# xcr3064xl_breakout.net
KiCad netlist of a schematic drawn in EAGLE
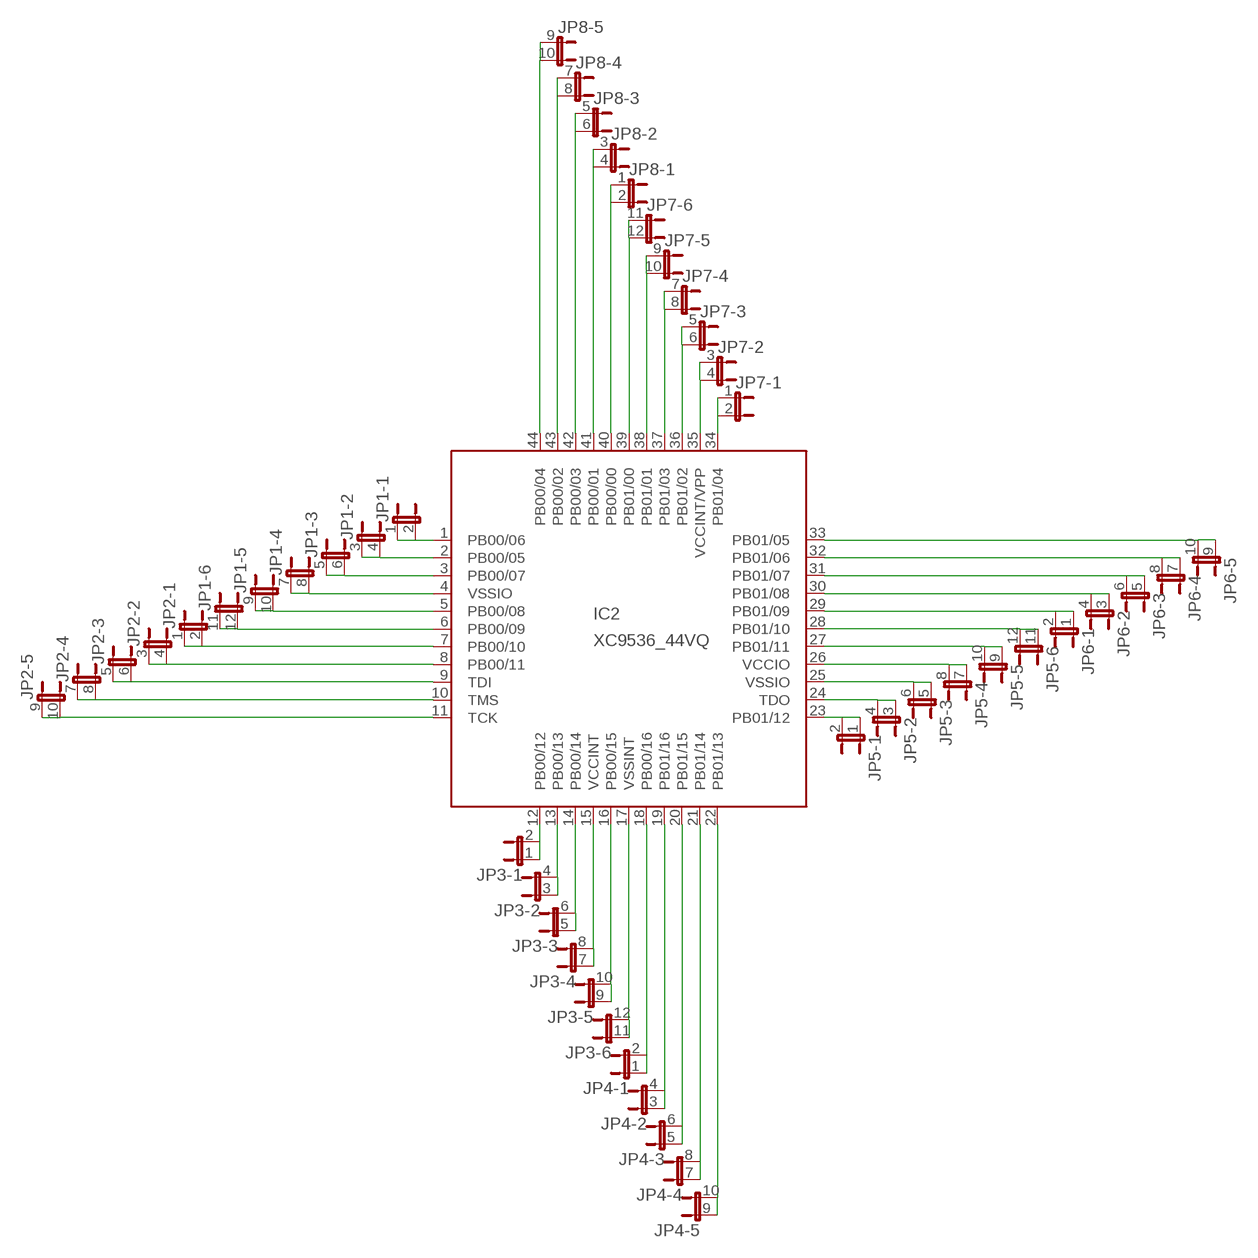
[diagram p0: schematic, sheet 1]

(export (version "E")
  (design (tool "Eeschema 10.0.6"))
  (components
    (comp (ref "IC2")
      (value "XC9536_44VQ")
      (footprint "eagle-import:SQFP-S-10X10-44")
      (fields (field (name "MPN") "XC9536-15VQG44C"))
      (libsource (lib "eagle-import") (part "XC9536_44VQ"))
    )
    (comp (ref "JP1")
      (value "JP6QE")
      (footprint "eagle-import:JP6Q")
      (libsource (lib "eagle-import") (part "JP6QE"))
    )
    (comp (ref "JP2")
      (value "JP6QE")
      (footprint "eagle-import:JP6Q")
      (libsource (lib "eagle-import") (part "JP6QE"))
    )
    (comp (ref "JP3")
      (value "JP6QE")
      (footprint "eagle-import:JP6Q")
      (libsource (lib "eagle-import") (part "JP6QE"))
    )
    (comp (ref "JP4")
      (value "JP6QE")
      (footprint "eagle-import:JP6Q")
      (libsource (lib "eagle-import") (part "JP6QE"))
    )
    (comp (ref "JP5")
      (value "JP6QE")
      (footprint "eagle-import:JP6Q")
      (libsource (lib "eagle-import") (part "JP6QE"))
    )
    (comp (ref "JP6")
      (value "JP6QE")
      (footprint "eagle-import:JP6Q")
      (libsource (lib "eagle-import") (part "JP6QE"))
    )
    (comp (ref "JP7")
      (value "JP6QE")
      (footprint "eagle-import:JP6Q")
      (libsource (lib "eagle-import") (part "JP6QE"))
    )
    (comp (ref "JP8")
      (value "JP6QE")
      (footprint "eagle-import:JP6Q")
      (libsource (lib "eagle-import") (part "JP6QE"))
    )
  )
  (nets
    (net (code "1") (name "Net-(IC2-PB00{slash}00)") (class "Default")
      (node (ref "IC2") (pin "40") (pinfunction "PB00/00_40") (pintype "bidirectional"))
      (node (ref "JP8") (pin "1") (pinfunction "1_1") (pintype "passive"))
      (node (ref "JP8") (pin "2") (pinfunction "2_2") (pintype "passive"))
    )
    (net (code "2") (name "Net-(IC2-PB00{slash}01)") (class "Default")
      (node (ref "IC2") (pin "41") (pinfunction "PB00/01_41") (pintype "bidirectional"))
      (node (ref "JP8") (pin "3") (pinfunction "1_3") (pintype "passive"))
      (node (ref "JP8") (pin "4") (pinfunction "2_4") (pintype "passive"))
    )
    (net (code "3") (name "Net-(IC2-PB00{slash}02)") (class "Default")
      (node (ref "IC2") (pin "43") (pinfunction "PB00/02_43") (pintype "bidirectional"))
      (node (ref "JP8") (pin "7") (pinfunction "1_7") (pintype "passive"))
      (node (ref "JP8") (pin "8") (pinfunction "2_8") (pintype "passive"))
    )
    (net (code "4") (name "Net-(IC2-PB00{slash}03)") (class "Default")
      (node (ref "IC2") (pin "42") (pinfunction "PB00/03_42") (pintype "bidirectional"))
      (node (ref "JP8") (pin "5") (pinfunction "1_5") (pintype "passive"))
      (node (ref "JP8") (pin "6") (pinfunction "2_6") (pintype "passive"))
    )
    (net (code "5") (name "Net-(IC2-PB00{slash}04)") (class "Default")
      (node (ref "IC2") (pin "44") (pinfunction "PB00/04_44") (pintype "bidirectional"))
      (node (ref "JP8") (pin "10") (pinfunction "2_10") (pintype "passive"))
      (node (ref "JP8") (pin "9") (pinfunction "1_9") (pintype "passive"))
    )
    (net (code "6") (name "Net-(IC2-PB00{slash}05)") (class "Default")
      (node (ref "IC2") (pin "2") (pinfunction "PB00/05_2") (pintype "bidirectional"))
      (node (ref "JP1") (pin "3") (pinfunction "1_3") (pintype "passive"))
      (node (ref "JP1") (pin "4") (pinfunction "2_4") (pintype "passive"))
    )
    (net (code "7") (name "Net-(IC2-PB00{slash}06)") (class "Default")
      (node (ref "IC2") (pin "1") (pinfunction "PB00/06_1") (pintype "bidirectional"))
      (node (ref "JP1") (pin "1") (pinfunction "1_1") (pintype "passive"))
      (node (ref "JP1") (pin "2") (pinfunction "2_2") (pintype "passive"))
    )
    (net (code "8") (name "Net-(IC2-PB00{slash}07)") (class "Default")
      (node (ref "IC2") (pin "3") (pinfunction "PB00/07_3") (pintype "bidirectional"))
      (node (ref "JP1") (pin "5") (pinfunction "1_5") (pintype "passive"))
      (node (ref "JP1") (pin "6") (pinfunction "2_6") (pintype "passive"))
    )
    (net (code "9") (name "Net-(IC2-PB00{slash}08)") (class "Default")
      (node (ref "IC2") (pin "5") (pinfunction "PB00/08_5") (pintype "bidirectional"))
      (node (ref "JP1") (pin "10") (pinfunction "2_10") (pintype "passive"))
      (node (ref "JP1") (pin "9") (pinfunction "1_9") (pintype "passive"))
    )
    (net (code "10") (name "Net-(IC2-PB00{slash}09)") (class "Default")
      (node (ref "IC2") (pin "6") (pinfunction "PB00/09_6") (pintype "bidirectional"))
      (node (ref "JP1") (pin "11") (pinfunction "1_11") (pintype "passive"))
      (node (ref "JP1") (pin "12") (pinfunction "2_12") (pintype "passive"))
    )
    (net (code "11") (name "Net-(IC2-PB00{slash}10)") (class "Default")
      (node (ref "IC2") (pin "7") (pinfunction "PB00/10_7") (pintype "bidirectional"))
      (node (ref "JP2") (pin "1") (pinfunction "1_1") (pintype "passive"))
      (node (ref "JP2") (pin "2") (pinfunction "2_2") (pintype "passive"))
    )
    (net (code "12") (name "Net-(IC2-PB00{slash}11)") (class "Default")
      (node (ref "IC2") (pin "8") (pinfunction "PB00/11_8") (pintype "bidirectional"))
      (node (ref "JP2") (pin "3") (pinfunction "1_3") (pintype "passive"))
      (node (ref "JP2") (pin "4") (pinfunction "2_4") (pintype "passive"))
    )
    (net (code "13") (name "Net-(IC2-PB00{slash}12)") (class "Default")
      (node (ref "IC2") (pin "12") (pinfunction "PB00/12_12") (pintype "bidirectional"))
      (node (ref "JP3") (pin "1") (pinfunction "1_1") (pintype "passive"))
      (node (ref "JP3") (pin "2") (pinfunction "2_2") (pintype "passive"))
    )
    (net (code "14") (name "Net-(IC2-PB00{slash}13)") (class "Default")
      (node (ref "IC2") (pin "13") (pinfunction "PB00/13_13") (pintype "bidirectional"))
      (node (ref "JP3") (pin "3") (pinfunction "1_3") (pintype "passive"))
      (node (ref "JP3") (pin "4") (pinfunction "2_4") (pintype "passive"))
    )
    (net (code "15") (name "Net-(IC2-PB00{slash}14)") (class "Default")
      (node (ref "IC2") (pin "14") (pinfunction "PB00/14_14") (pintype "bidirectional"))
      (node (ref "JP3") (pin "5") (pinfunction "1_5") (pintype "passive"))
      (node (ref "JP3") (pin "6") (pinfunction "2_6") (pintype "passive"))
    )
    (net (code "16") (name "Net-(IC2-PB00{slash}15)") (class "Default")
      (node (ref "IC2") (pin "16") (pinfunction "PB00/15_16") (pintype "bidirectional"))
      (node (ref "JP3") (pin "10") (pinfunction "2_10") (pintype "passive"))
      (node (ref "JP3") (pin "9") (pinfunction "1_9") (pintype "passive"))
    )
    (net (code "17") (name "Net-(IC2-PB00{slash}16)") (class "Default")
      (node (ref "IC2") (pin "18") (pinfunction "PB00/16_18") (pintype "bidirectional"))
      (node (ref "JP4") (pin "1") (pinfunction "1_1") (pintype "passive"))
      (node (ref "JP4") (pin "2") (pinfunction "2_2") (pintype "passive"))
    )
    (net (code "18") (name "Net-(IC2-PB01{slash}00)") (class "Default")
      (node (ref "IC2") (pin "39") (pinfunction "PB01/00_39") (pintype "bidirectional"))
      (node (ref "JP7") (pin "11") (pinfunction "1_11") (pintype "passive"))
      (node (ref "JP7") (pin "12") (pinfunction "2_12") (pintype "passive"))
    )
    (net (code "19") (name "Net-(IC2-PB01{slash}01)") (class "Default")
      (node (ref "IC2") (pin "38") (pinfunction "PB01/01_38") (pintype "bidirectional"))
      (node (ref "JP7") (pin "10") (pinfunction "2_10") (pintype "passive"))
      (node (ref "JP7") (pin "9") (pinfunction "1_9") (pintype "passive"))
    )
    (net (code "20") (name "Net-(IC2-PB01{slash}02)") (class "Default")
      (node (ref "IC2") (pin "36") (pinfunction "PB01/02_36") (pintype "bidirectional"))
      (node (ref "JP7") (pin "5") (pinfunction "1_5") (pintype "passive"))
      (node (ref "JP7") (pin "6") (pinfunction "2_6") (pintype "passive"))
    )
    (net (code "21") (name "Net-(IC2-PB01{slash}03)") (class "Default")
      (node (ref "IC2") (pin "37") (pinfunction "PB01/03_37") (pintype "bidirectional"))
      (node (ref "JP7") (pin "7") (pinfunction "1_7") (pintype "passive"))
      (node (ref "JP7") (pin "8") (pinfunction "2_8") (pintype "passive"))
    )
    (net (code "22") (name "Net-(IC2-PB01{slash}04)") (class "Default")
      (node (ref "IC2") (pin "34") (pinfunction "PB01/04_34") (pintype "bidirectional"))
      (node (ref "JP7") (pin "1") (pinfunction "1_1") (pintype "passive"))
      (node (ref "JP7") (pin "2") (pinfunction "2_2") (pintype "passive"))
    )
    (net (code "23") (name "Net-(IC2-PB01{slash}05)") (class "Default")
      (node (ref "IC2") (pin "33") (pinfunction "PB01/05_33") (pintype "bidirectional"))
      (node (ref "JP6") (pin "10") (pinfunction "2_10") (pintype "passive"))
      (node (ref "JP6") (pin "9") (pinfunction "1_9") (pintype "passive"))
    )
    (net (code "24") (name "Net-(IC2-PB01{slash}06)") (class "Default")
      (node (ref "IC2") (pin "32") (pinfunction "PB01/06_32") (pintype "bidirectional"))
      (node (ref "JP6") (pin "7") (pinfunction "1_7") (pintype "passive"))
      (node (ref "JP6") (pin "8") (pinfunction "2_8") (pintype "passive"))
    )
    (net (code "25") (name "Net-(IC2-PB01{slash}07)") (class "Default")
      (node (ref "IC2") (pin "31") (pinfunction "PB01/07_31") (pintype "bidirectional"))
      (node (ref "JP6") (pin "5") (pinfunction "1_5") (pintype "passive"))
      (node (ref "JP6") (pin "6") (pinfunction "2_6") (pintype "passive"))
    )
    (net (code "26") (name "Net-(IC2-PB01{slash}08)") (class "Default")
      (node (ref "IC2") (pin "30") (pinfunction "PB01/08_30") (pintype "bidirectional"))
      (node (ref "JP6") (pin "3") (pinfunction "1_3") (pintype "passive"))
      (node (ref "JP6") (pin "4") (pinfunction "2_4") (pintype "passive"))
    )
    (net (code "27") (name "Net-(IC2-PB01{slash}09)") (class "Default")
      (node (ref "IC2") (pin "29") (pinfunction "PB01/09_29") (pintype "bidirectional"))
      (node (ref "JP6") (pin "1") (pinfunction "1_1") (pintype "passive"))
      (node (ref "JP6") (pin "2") (pinfunction "2_2") (pintype "passive"))
    )
    (net (code "28") (name "Net-(IC2-PB01{slash}10)") (class "Default")
      (node (ref "IC2") (pin "28") (pinfunction "PB01/10_28") (pintype "bidirectional"))
      (node (ref "JP5") (pin "11") (pinfunction "1_11") (pintype "passive"))
      (node (ref "JP5") (pin "12") (pinfunction "2_12") (pintype "passive"))
    )
    (net (code "29") (name "Net-(IC2-PB01{slash}11)") (class "Default")
      (node (ref "IC2") (pin "27") (pinfunction "PB01/11_27") (pintype "bidirectional"))
      (node (ref "JP5") (pin "10") (pinfunction "2_10") (pintype "passive"))
      (node (ref "JP5") (pin "9") (pinfunction "1_9") (pintype "passive"))
    )
    (net (code "30") (name "Net-(IC2-PB01{slash}12)") (class "Default")
      (node (ref "IC2") (pin "23") (pinfunction "PB01/12_23") (pintype "bidirectional"))
      (node (ref "JP5") (pin "1") (pinfunction "1_1") (pintype "passive"))
      (node (ref "JP5") (pin "2") (pinfunction "2_2") (pintype "passive"))
    )
    (net (code "31") (name "Net-(IC2-PB01{slash}13)") (class "Default")
      (node (ref "IC2") (pin "22") (pinfunction "PB01/13_22") (pintype "bidirectional"))
      (node (ref "JP4") (pin "10") (pinfunction "2_10") (pintype "passive"))
      (node (ref "JP4") (pin "9") (pinfunction "1_9") (pintype "passive"))
    )
    (net (code "32") (name "Net-(IC2-PB01{slash}14)") (class "Default")
      (node (ref "IC2") (pin "21") (pinfunction "PB01/14_21") (pintype "bidirectional"))
      (node (ref "JP4") (pin "7") (pinfunction "1_7") (pintype "passive"))
      (node (ref "JP4") (pin "8") (pinfunction "2_8") (pintype "passive"))
    )
    (net (code "33") (name "Net-(IC2-PB01{slash}15)") (class "Default")
      (node (ref "IC2") (pin "20") (pinfunction "PB01/15_20") (pintype "bidirectional"))
      (node (ref "JP4") (pin "5") (pinfunction "1_5") (pintype "passive"))
      (node (ref "JP4") (pin "6") (pinfunction "2_6") (pintype "passive"))
    )
    (net (code "34") (name "Net-(IC2-PB01{slash}16)") (class "Default")
      (node (ref "IC2") (pin "19") (pinfunction "PB01/16_19") (pintype "bidirectional"))
      (node (ref "JP4") (pin "3") (pinfunction "1_3") (pintype "passive"))
      (node (ref "JP4") (pin "4") (pinfunction "2_4") (pintype "passive"))
    )
    (net (code "35") (name "Net-(IC2-TCK)") (class "Default")
      (node (ref "IC2") (pin "11") (pinfunction "TCK_11") (pintype "input"))
      (node (ref "JP2") (pin "10") (pinfunction "2_10") (pintype "passive"))
      (node (ref "JP2") (pin "9") (pinfunction "1_9") (pintype "passive"))
    )
    (net (code "36") (name "Net-(IC2-TDI)") (class "Default")
      (node (ref "IC2") (pin "9") (pinfunction "TDI_9") (pintype "input"))
      (node (ref "JP2") (pin "5") (pinfunction "1_5") (pintype "passive"))
      (node (ref "JP2") (pin "6") (pinfunction "2_6") (pintype "passive"))
    )
    (net (code "37") (name "Net-(IC2-TDO)") (class "Default")
      (node (ref "IC2") (pin "24") (pinfunction "TDO_24") (pintype "output"))
      (node (ref "JP5") (pin "3") (pinfunction "1_3") (pintype "passive"))
      (node (ref "JP5") (pin "4") (pinfunction "2_4") (pintype "passive"))
    )
    (net (code "38") (name "Net-(IC2-TMS)") (class "Default")
      (node (ref "IC2") (pin "10") (pinfunction "TMS_10") (pintype "input"))
      (node (ref "JP2") (pin "7") (pinfunction "1_7") (pintype "passive"))
      (node (ref "JP2") (pin "8") (pinfunction "2_8") (pintype "passive"))
    )
    (net (code "39") (name "Net-(IC2-VCCINT)") (class "Default")
      (node (ref "IC2") (pin "15") (pinfunction "VCCINT_15") (pintype "power_in"))
      (node (ref "JP3") (pin "7") (pinfunction "1_7") (pintype "passive"))
      (node (ref "JP3") (pin "8") (pinfunction "2_8") (pintype "passive"))
    )
    (net (code "40") (name "Net-(IC2-VCCINT{slash}VPP)") (class "Default")
      (node (ref "IC2") (pin "35") (pinfunction "VCCINT/VPP_35") (pintype "input"))
      (node (ref "JP7") (pin "3") (pinfunction "1_3") (pintype "passive"))
      (node (ref "JP7") (pin "4") (pinfunction "2_4") (pintype "passive"))
    )
    (net (code "41") (name "Net-(IC2-VCCIO)") (class "Default")
      (node (ref "IC2") (pin "26") (pinfunction "VCCIO_26") (pintype "power_in"))
      (node (ref "JP5") (pin "7") (pinfunction "1_7") (pintype "passive"))
      (node (ref "JP5") (pin "8") (pinfunction "2_8") (pintype "passive"))
    )
    (net (code "42") (name "Net-(IC2-VSSINT)") (class "Default")
      (node (ref "IC2") (pin "17") (pinfunction "VSSINT_17") (pintype "power_in"))
      (node (ref "JP3") (pin "11") (pinfunction "1_11") (pintype "passive"))
      (node (ref "JP3") (pin "12") (pinfunction "2_12") (pintype "passive"))
    )
    (net (code "43") (name "Net-(JP1D-1)") (class "Default")
      (node (ref "IC2") (pin "4") (pinfunction "VSSIO_4") (pintype "power_in"))
      (node (ref "JP1") (pin "7") (pinfunction "1_7") (pintype "passive"))
      (node (ref "JP1") (pin "8") (pinfunction "2_8") (pintype "passive"))
    )
    (net (code "44") (name "Net-(JP5C-1)") (class "Default")
      (node (ref "IC2") (pin "25") (pinfunction "VSSIO_25") (pintype "power_in"))
      (node (ref "JP5") (pin "5") (pinfunction "1_5") (pintype "passive"))
      (node (ref "JP5") (pin "6") (pinfunction "2_6") (pintype "passive"))
    )
  )
)
